# Arduino_thermcouple.net
KiCad netlist of a schematic drawn in EAGLE
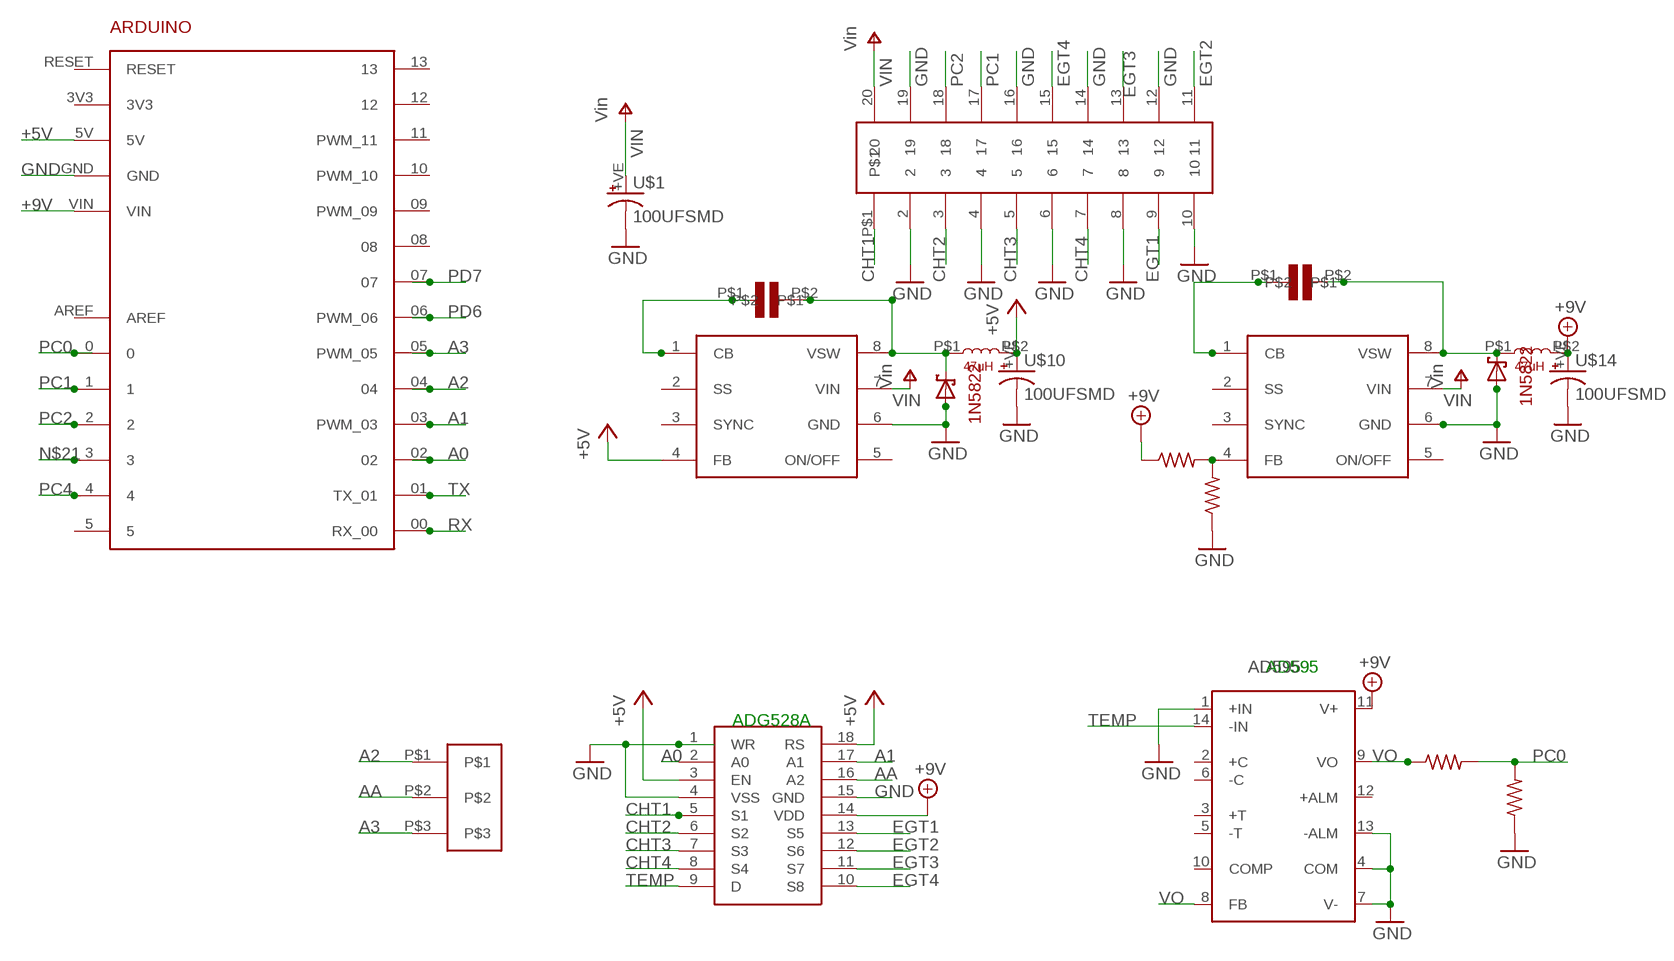
[diagram p0: schematic, sheet 1]

(export (version "E")
  (design (tool "Eeschema 10.0.6"))
  (components
    (comp (ref "\"")
      (value "ADG528A")
      (footprint "eagle-import:DIL18")
      (libsource (lib "eagle-import") (part "ADG528A"))
    )
    (comp (ref "ARDUINO2")
      (value "ARDUINO")
      (footprint "eagle-import:ARDUINO")
      (libsource (lib "eagle-import") (part "ARDUINO"))
    )
    (comp (ref "IC2")
      (value "AD595")
      (footprint "eagle-import:DIL14")
      (fields (field (name "MPN") "AD595AQ"))
      (libsource (lib "eagle-import") (part "AD595"))
    )
    (comp (ref "R5")
      (value "10K")
      (footprint "eagle-import:0.3RESISTOR")
      (libsource (lib "eagle-import") (part "0.3RESISTOR"))
    )
    (comp (ref "R6")
      (value "10K")
      (footprint "eagle-import:0.3RESISTOR")
      (libsource (lib "eagle-import") (part "0.3RESISTOR"))
    )
    (comp (ref "U$1")
      (value "100UFSMD")
      (footprint "eagle-import:100UFSMD")
      (libsource (lib "eagle-import") (part "100UFSMD"))
    )
    (comp (ref "U$2")
      (value "1N5822")
      (footprint "eagle-import:1N5822")
      (libsource (lib "eagle-import") (part "1N5822"))
    )
    (comp (ref "U$3")
      (value "LM2672")
      (footprint "eagle-import:DIL08")
      (libsource (lib "eagle-import") (part "LM2672"))
    )
    (comp (ref "U$4")
      (value "1N5822")
      (footprint "eagle-import:1N5822")
      (libsource (lib "eagle-import") (part "1N5822"))
    )
    (comp (ref "U$5")
      (value "01CAP")
      (footprint "eagle-import:01CAP")
      (libsource (lib "eagle-import") (part "01CAP"))
    )
    (comp (ref "U$6")
      (value "LM2672")
      (footprint "eagle-import:DIL08")
      (libsource (lib "eagle-import") (part "LM2672"))
    )
    (comp (ref "U$7")
      (value "01CAP")
      (footprint "eagle-import:01CAP")
      (libsource (lib "eagle-import") (part "01CAP"))
    )
    (comp (ref "U$8")
      (value "20PIN0.1INCH")
      (footprint "eagle-import:20PIN0.1INCH")
      (libsource (lib "eagle-import") (part "20PIN0.1INCH"))
    )
    (comp (ref "U$9")
      (value "47uH")
      (footprint "eagle-import:47UHSMD")
      (libsource (lib "eagle-import") (part "47UHSMD"))
    )
    (comp (ref "U$10")
      (value "100UFSMD")
      (footprint "eagle-import:100UFSMD")
      (libsource (lib "eagle-import") (part "100UFSMD"))
    )
    (comp (ref "U$13")
      (value "47uH")
      (footprint "eagle-import:47UHSMD")
      (libsource (lib "eagle-import") (part "47UHSMD"))
    )
    (comp (ref "U$14")
      (value "100UFSMD")
      (footprint "eagle-import:100UFSMD")
      (libsource (lib "eagle-import") (part "100UFSMD"))
    )
    (comp (ref "U$15")
      (value "1K5")
      (footprint "eagle-import:0.3RESISTOR")
      (libsource (lib "eagle-import") (part "0.3RESISTOR"))
    )
    (comp (ref "U$16")
      (value "10K")
      (footprint "eagle-import:0.3RESISTOR")
      (libsource (lib "eagle-import") (part "0.3RESISTOR"))
    )
    (comp (ref "U$17")
      (value "3PINHEADER")
      (footprint "eagle-import:3PINHEADER")
      (libsource (lib "eagle-import") (part "3PINHEADER"))
    )
  )
  (nets
    (net (code "1") (name "+5V") (class "Default")
      (node (ref "\"") (pin "18") (pinfunction "RS_18") (pintype "bidirectional"))
      (node (ref "\"") (pin "3") (pinfunction "EN_3") (pintype "bidirectional"))
      (node (ref "ARDUINO2") (pin "5V") (pinfunction "5V_5V") (pintype "bidirectional"))
      (node (ref "U$10") (pin "+VE") (pinfunction "+_+VE") (pintype "passive"))
      (node (ref "U$3") (pin "4") (pinfunction "FB_4") (pintype "bidirectional"))
      (node (ref "U$9") (pin "P$2") (pinfunction "2_P$2") (pintype "passive"))
    )
    (net (code "2") (name "+9V") (class "Default")
      (node (ref "\"") (pin "14") (pinfunction "VDD_14") (pintype "bidirectional"))
      (node (ref "ARDUINO2") (pin "VIN") (pinfunction "VIN_VIN") (pintype "bidirectional"))
      (node (ref "IC2") (pin "11") (pinfunction "V+_11") (pintype "power_in"))
      (node (ref "U$13") (pin "P$2") (pinfunction "2_P$2") (pintype "passive"))
      (node (ref "U$14") (pin "+VE") (pinfunction "+_+VE") (pintype "passive"))
      (node (ref "U$16") (pin "P$1") (pinfunction "1_P$1") (pintype "passive"))
    )
    (net (code "3") (name "/A0") (class "Default")
      (node (ref "\"") (pin "2") (pinfunction "A0_2") (pintype "bidirectional"))
      (node (ref "ARDUINO2") (pin "02") (pinfunction "02_02") (pintype "bidirectional"))
    )
    (net (code "4") (name "/A1") (class "Default")
      (node (ref "\"") (pin "17") (pinfunction "A1_17") (pintype "bidirectional"))
      (node (ref "ARDUINO2") (pin "03") (pinfunction "PWM_03_03") (pintype "bidirectional"))
    )
    (net (code "5") (name "/A2") (class "Default")
      (node (ref "ARDUINO2") (pin "04") (pinfunction "04_04") (pintype "bidirectional"))
      (node (ref "U$17") (pin "P$1") (pinfunction "P$1_P$1") (pintype "bidirectional"))
    )
    (net (code "6") (name "/A3") (class "Default")
      (node (ref "ARDUINO2") (pin "05") (pinfunction "PWM_05_05") (pintype "bidirectional"))
      (node (ref "U$17") (pin "P$3") (pinfunction "P$3_P$3") (pintype "bidirectional"))
    )
    (net (code "7") (name "/AA") (class "Default")
      (node (ref "\"") (pin "16") (pinfunction "A2_16") (pintype "bidirectional"))
      (node (ref "U$17") (pin "P$2") (pinfunction "P$2_P$2") (pintype "bidirectional"))
    )
    (net (code "8") (name "/CHT1") (class "Default")
      (node (ref "\"") (pin "5") (pinfunction "S1_5") (pintype "bidirectional"))
      (node (ref "U$8") (pin "P$1") (pinfunction "P$1_P$1") (pintype "bidirectional"))
    )
    (net (code "9") (name "/CHT2") (class "Default")
      (node (ref "\"") (pin "6") (pinfunction "S2_6") (pintype "bidirectional"))
      (node (ref "U$8") (pin "3") (pinfunction "3_3") (pintype "bidirectional"))
    )
    (net (code "10") (name "/CHT3") (class "Default")
      (node (ref "\"") (pin "7") (pinfunction "S3_7") (pintype "bidirectional"))
      (node (ref "U$8") (pin "5") (pinfunction "5_5") (pintype "bidirectional"))
    )
    (net (code "11") (name "/CHT4") (class "Default")
      (node (ref "\"") (pin "8") (pinfunction "S4_8") (pintype "bidirectional"))
      (node (ref "U$8") (pin "7") (pinfunction "7_7") (pintype "bidirectional"))
    )
    (net (code "12") (name "/EGT1") (class "Default")
      (node (ref "\"") (pin "13") (pinfunction "S5_13") (pintype "bidirectional"))
      (node (ref "U$8") (pin "9") (pinfunction "9_9") (pintype "bidirectional"))
    )
    (net (code "13") (name "/EGT2") (class "Default")
      (node (ref "\"") (pin "12") (pinfunction "S6_12") (pintype "bidirectional"))
      (node (ref "U$8") (pin "11") (pinfunction "11_11") (pintype "bidirectional"))
    )
    (net (code "14") (name "/EGT3") (class "Default")
      (node (ref "\"") (pin "11") (pinfunction "S7_11") (pintype "bidirectional"))
      (node (ref "U$8") (pin "13") (pinfunction "13_13") (pintype "bidirectional"))
    )
    (net (code "15") (name "/EGT4") (class "Default")
      (node (ref "\"") (pin "10") (pinfunction "S8_10") (pintype "bidirectional"))
      (node (ref "U$8") (pin "15") (pinfunction "15_15") (pintype "bidirectional"))
    )
    (net (code "16") (name "/N$21") (class "Default")
      (node (ref "ARDUINO2") (pin "3") (pinfunction "3_3") (pintype "bidirectional"))
    )
    (net (code "17") (name "/PC0") (class "Default")
      (node (ref "ARDUINO2") (pin "0") (pinfunction "0_0") (pintype "bidirectional"))
      (node (ref "R5") (pin "P$2") (pinfunction "2_P$2") (pintype "passive"))
      (node (ref "R6") (pin "P$2") (pinfunction "2_P$2") (pintype "passive"))
    )
    (net (code "18") (name "/PC1") (class "Default")
      (node (ref "ARDUINO2") (pin "1") (pinfunction "1_1") (pintype "bidirectional"))
      (node (ref "U$8") (pin "17") (pinfunction "17_17") (pintype "bidirectional"))
    )
    (net (code "19") (name "/PC2") (class "Default")
      (node (ref "ARDUINO2") (pin "2") (pinfunction "2_2") (pintype "bidirectional"))
      (node (ref "U$8") (pin "18") (pinfunction "18_18") (pintype "bidirectional"))
    )
    (net (code "20") (name "/PC4") (class "Default")
      (node (ref "ARDUINO2") (pin "4") (pinfunction "4_4") (pintype "bidirectional"))
    )
    (net (code "21") (name "/PD6") (class "Default")
      (node (ref "ARDUINO2") (pin "06") (pinfunction "PWM_06_06") (pintype "bidirectional"))
    )
    (net (code "22") (name "/PD7") (class "Default")
      (node (ref "ARDUINO2") (pin "07") (pinfunction "07_07") (pintype "bidirectional"))
    )
    (net (code "23") (name "/RX") (class "Default")
      (node (ref "ARDUINO2") (pin "00") (pinfunction "RX_00_00") (pintype "bidirectional"))
    )
    (net (code "24") (name "/TEMP") (class "Default")
      (node (ref "\"") (pin "9") (pinfunction "D_9") (pintype "bidirectional"))
      (node (ref "IC2") (pin "14") (pinfunction "-IN_14") (pintype "input"))
    )
    (net (code "25") (name "/TX") (class "Default")
      (node (ref "ARDUINO2") (pin "01") (pinfunction "TX_01_01") (pintype "bidirectional"))
    )
    (net (code "26") (name "/VO") (class "Default")
      (node (ref "IC2") (pin "8") (pinfunction "FB_8") (pintype "passive"))
      (node (ref "IC2") (pin "9") (pinfunction "VO_9") (pintype "output"))
      (node (ref "R5") (pin "P$1") (pinfunction "1_P$1") (pintype "passive"))
    )
    (net (code "27") (name "GND") (class "Default")
      (node (ref "\"") (pin "1") (pinfunction "WR_1") (pintype "bidirectional"))
      (node (ref "\"") (pin "15") (pinfunction "GND_15") (pintype "bidirectional"))
      (node (ref "\"") (pin "4") (pinfunction "VSS_4") (pintype "bidirectional"))
      (node (ref "ARDUINO2") (pin "GND") (pinfunction "GND_GND") (pintype "bidirectional"))
      (node (ref "IC2") (pin "1") (pinfunction "+IN_1") (pintype "input"))
      (node (ref "IC2") (pin "13") (pinfunction "-ALM_13") (pintype "passive"))
      (node (ref "IC2") (pin "4") (pinfunction "COM_4") (pintype "power_in"))
      (node (ref "IC2") (pin "7") (pinfunction "V-_7") (pintype "power_in"))
      (node (ref "R6") (pin "P$1") (pinfunction "1_P$1") (pintype "passive"))
      (node (ref "U$1") (pin "-VE") (pinfunction "-_-VE") (pintype "passive"))
      (node (ref "U$10") (pin "-VE") (pinfunction "-_-VE") (pintype "passive"))
      (node (ref "U$14") (pin "-VE") (pinfunction "-_-VE") (pintype "passive"))
      (node (ref "U$15") (pin "P$1") (pinfunction "1_P$1") (pintype "passive"))
      (node (ref "U$2") (pin "A") (pinfunction "A_A") (pintype "passive"))
      (node (ref "U$3") (pin "6") (pinfunction "GND_6") (pintype "bidirectional"))
      (node (ref "U$4") (pin "A") (pinfunction "A_A") (pintype "passive"))
      (node (ref "U$6") (pin "6") (pinfunction "GND_6") (pintype "bidirectional"))
      (node (ref "U$8") (pin "10") (pinfunction "10_10") (pintype "bidirectional"))
      (node (ref "U$8") (pin "12") (pinfunction "12_12") (pintype "bidirectional"))
      (node (ref "U$8") (pin "14") (pinfunction "14_14") (pintype "bidirectional"))
      (node (ref "U$8") (pin "16") (pinfunction "16_16") (pintype "bidirectional"))
      (node (ref "U$8") (pin "19") (pinfunction "19_19") (pintype "bidirectional"))
      (node (ref "U$8") (pin "2") (pinfunction "2_2") (pintype "bidirectional"))
      (node (ref "U$8") (pin "4") (pinfunction "4_4") (pintype "bidirectional"))
      (node (ref "U$8") (pin "6") (pinfunction "6_6") (pintype "bidirectional"))
      (node (ref "U$8") (pin "8") (pinfunction "8_8") (pintype "bidirectional"))
    )
    (net (code "28") (name "Net-(U$2-C)") (class "Default")
      (node (ref "U$2") (pin "K") (pinfunction "C_K") (pintype "passive"))
      (node (ref "U$3") (pin "8") (pinfunction "VSW_8") (pintype "bidirectional"))
      (node (ref "U$5") (pin "P$2") (pinfunction "P$2_P$2") (pintype "passive"))
      (node (ref "U$9") (pin "P$1") (pinfunction "1_P$1") (pintype "passive"))
    )
    (net (code "29") (name "Net-(U$3-CB)") (class "Default")
      (node (ref "U$3") (pin "1") (pinfunction "CB_1") (pintype "bidirectional"))
      (node (ref "U$5") (pin "P$1") (pinfunction "P$1_P$1") (pintype "passive"))
    )
    (net (code "30") (name "Net-(U$6-CB)") (class "Default")
      (node (ref "U$6") (pin "1") (pinfunction "CB_1") (pintype "bidirectional"))
      (node (ref "U$7") (pin "P$1") (pinfunction "P$1_P$1") (pintype "passive"))
    )
    (net (code "31") (name "Net-(U$13-1)") (class "Default")
      (node (ref "U$13") (pin "P$1") (pinfunction "1_P$1") (pintype "passive"))
      (node (ref "U$4") (pin "K") (pinfunction "C_K") (pintype "passive"))
      (node (ref "U$6") (pin "8") (pinfunction "VSW_8") (pintype "bidirectional"))
      (node (ref "U$7") (pin "P$2") (pinfunction "P$2_P$2") (pintype "passive"))
    )
    (net (code "32") (name "Net-(U$15-2)") (class "Default")
      (node (ref "U$15") (pin "P$2") (pinfunction "2_P$2") (pintype "passive"))
      (node (ref "U$16") (pin "P$2") (pinfunction "2_P$2") (pintype "passive"))
      (node (ref "U$6") (pin "4") (pinfunction "FB_4") (pintype "bidirectional"))
    )
    (net (code "33") (name "V+") (class "Default")
      (node (ref "U$1") (pin "+VE") (pinfunction "+_+VE") (pintype "passive"))
      (node (ref "U$3") (pin "7") (pinfunction "VIN_7") (pintype "bidirectional"))
      (node (ref "U$6") (pin "7") (pinfunction "VIN_7") (pintype "bidirectional"))
      (node (ref "U$8") (pin "20") (pinfunction "20_20") (pintype "bidirectional"))
    )
    (net (code "34") (name "unconnected-(ARDUINO2-PWM_09-Pad09)") (class "Default")
      (node (ref "ARDUINO2") (pin "09") (pinfunction "PWM_09_09") (pintype "bidirectional"))
    )
    (net (code "35") (name "unconnected-(ARDUINO2-PWM_10-Pad10)") (class "Default")
      (node (ref "ARDUINO2") (pin "10") (pinfunction "PWM_10_10") (pintype "bidirectional"))
    )
    (net (code "36") (name "unconnected-(ARDUINO2-PWM_11-Pad11)") (class "Default")
      (node (ref "ARDUINO2") (pin "11") (pinfunction "PWM_11_11") (pintype "bidirectional"))
    )
    (net (code "37") (name "unconnected-(ARDUINO2-Pad3V3)") (class "Default")
      (node (ref "ARDUINO2") (pin "3V3") (pinfunction "3V3_3V3") (pintype "bidirectional"))
    )
    (net (code "38") (name "unconnected-(ARDUINO2-Pad5)") (class "Default")
      (node (ref "ARDUINO2") (pin "5") (pinfunction "5_5") (pintype "bidirectional"))
    )
    (net (code "39") (name "unconnected-(ARDUINO2-Pad08)") (class "Default")
      (node (ref "ARDUINO2") (pin "08") (pinfunction "08_08") (pintype "bidirectional"))
    )
    (net (code "40") (name "unconnected-(ARDUINO2-Pad12)") (class "Default")
      (node (ref "ARDUINO2") (pin "12") (pinfunction "12_12") (pintype "bidirectional"))
    )
    (net (code "41") (name "unconnected-(ARDUINO2-Pad13)") (class "Default")
      (node (ref "ARDUINO2") (pin "13") (pinfunction "13_13") (pintype "bidirectional"))
    )
    (net (code "42") (name "unconnected-(ARDUINO2-PadAREF)") (class "Default")
      (node (ref "ARDUINO2") (pin "AREF") (pinfunction "AREF_AREF") (pintype "bidirectional"))
    )
    (net (code "43") (name "unconnected-(ARDUINO2-PadRESET)") (class "Default")
      (node (ref "ARDUINO2") (pin "RESET") (pinfunction "RESET_RESET") (pintype "bidirectional"))
    )
    (net (code "44") (name "unconnected-(IC2-+ALM-Pad12)") (class "Default")
      (node (ref "IC2") (pin "12") (pinfunction "+ALM_12") (pintype "passive"))
    )
    (net (code "45") (name "unconnected-(IC2-+C-Pad2)") (class "Default")
      (node (ref "IC2") (pin "2") (pinfunction "+C_2") (pintype "input"))
    )
    (net (code "46") (name "unconnected-(IC2-+T-Pad3)") (class "Default")
      (node (ref "IC2") (pin "3") (pinfunction "+T_3") (pintype "passive"))
    )
    (net (code "47") (name "unconnected-(IC2--C-Pad6)") (class "Default")
      (node (ref "IC2") (pin "6") (pinfunction "-C_6") (pintype "input"))
    )
    (net (code "48") (name "unconnected-(IC2--T-Pad5)") (class "Default")
      (node (ref "IC2") (pin "5") (pinfunction "-T_5") (pintype "passive"))
    )
    (net (code "49") (name "unconnected-(IC2-COMP-Pad10)") (class "Default")
      (node (ref "IC2") (pin "10") (pinfunction "COMP_10") (pintype "passive"))
    )
    (net (code "50") (name "unconnected-(U$3-ON{slash}OFF-Pad5)") (class "Default")
      (node (ref "U$3") (pin "5") (pinfunction "ON/OFF_5") (pintype "bidirectional"))
    )
    (net (code "51") (name "unconnected-(U$3-SS-Pad2)") (class "Default")
      (node (ref "U$3") (pin "2") (pinfunction "SS_2") (pintype "bidirectional"))
    )
    (net (code "52") (name "unconnected-(U$3-SYNC-Pad3)") (class "Default")
      (node (ref "U$3") (pin "3") (pinfunction "SYNC_3") (pintype "bidirectional"))
    )
    (net (code "53") (name "unconnected-(U$6-ON{slash}OFF-Pad5)") (class "Default")
      (node (ref "U$6") (pin "5") (pinfunction "ON/OFF_5") (pintype "bidirectional"))
    )
    (net (code "54") (name "unconnected-(U$6-SS-Pad2)") (class "Default")
      (node (ref "U$6") (pin "2") (pinfunction "SS_2") (pintype "bidirectional"))
    )
    (net (code "55") (name "unconnected-(U$6-SYNC-Pad3)") (class "Default")
      (node (ref "U$6") (pin "3") (pinfunction "SYNC_3") (pintype "bidirectional"))
    )
  )
)
